# PowerDACSUB.net
KiCad netlist of a schematic drawn in Altium Designer
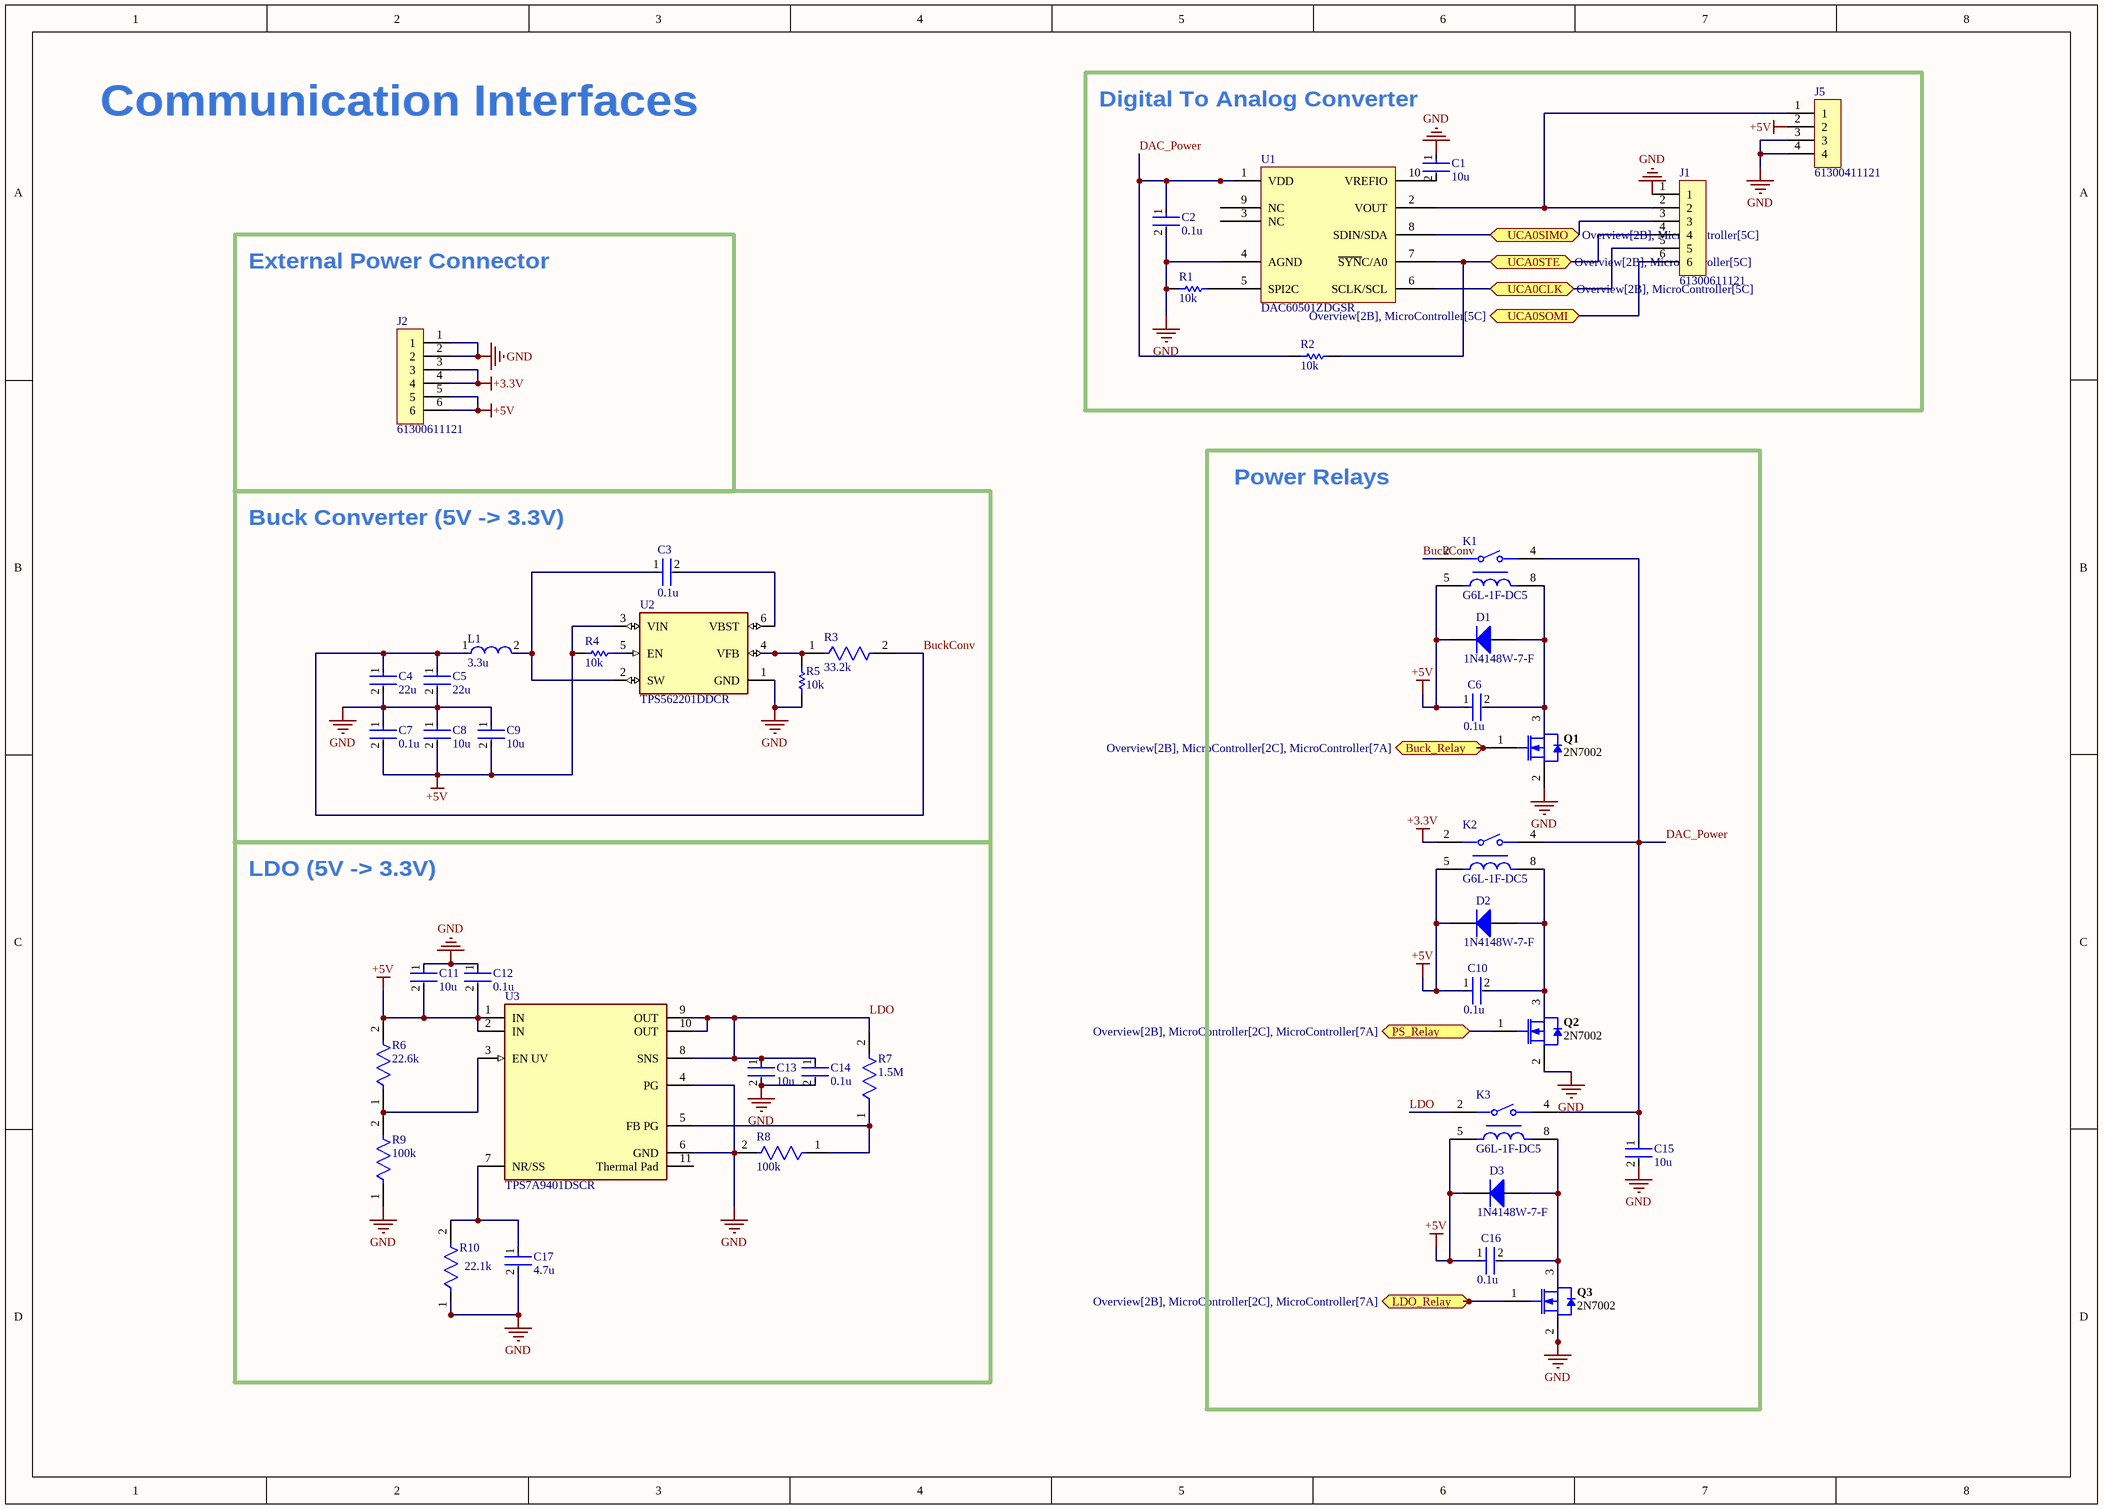
[diagram p0: PowerDACSUB.SchDoc]

(export (version "E")
  (design (tool "Eeschema 10.0.6"))
  (components
    (comp (ref "C1")
      (value "10u")
      (footprint "FP-CL21-IPC_A")
      (description "CL21 Series 0805 10uF 25V ±10% Tolerance X5R Multilayer Ceramic Chip Capacitor")
      (fields (field (name "TOLERANCE") "10%"))
      (libsource (lib "Altium Content Vault") (part "b4654b650e69147ec39a6b967a45e02"))
    )
    (comp (ref "C2")
      (value "0.1u")
      (footprint "FP-CC0805-0_85-MFG")
      (description "CAP CER 0.1UF 50V X7R 0805")
      (fields (field (name "TOLERANCE") "0.1") (field (name "MANUFACTURER PART NUMBER") "CC0805KRX7R9BB104"))
      (libsource (lib "Altium Content Vault") (part "11868f565c42a9108669ba33697ecf6"))
    )
    (comp (ref "C3")
      (value "0.1u")
      (footprint "FP-CC0805-0_85-MFG")
      (fields
        (field (name "TOLERANCE") "0.1")
        (field (name "MANUFACTURER PART NUMBER") "CC0805KRX7R9BB104")
        (field (name "MANUFACTURER") "Yageo")
      )
      (libsource (lib "Altium Content Vault") (part "11868f565c42a9108669ba33697ecf6"))
    )
    (comp (ref "C4")
      (value "22u")
      (footprint "FP-CL32-IPC_C")
      (description "Cap Ceramic 22uF 16V X7R ±10% SMD 1210 +125°C Embossed T/R")
      (fields (field (name "TOLERANCE") "10%") (field (name "VOLTAGE") "10V"))
      (libsource (lib "Altium Content Vault") (part "b4654b650e69147ec39a6b967a45e02"))
    )
    (comp (ref "C5")
      (value "22u")
      (footprint "FP-CL32-IPC_C")
      (description "Cap Ceramic 22uF 16V X7R ±10% SMD 1210 +125°C Embossed T/R")
      (fields (field (name "TOLERANCE") "10%") (field (name "VOLTAGE") "10V"))
      (libsource (lib "Altium Content Vault") (part "b4654b650e69147ec39a6b967a45e02"))
    )
    (comp (ref "C6")
      (value "0.1u")
      (footprint "FP-CC0805-0_85-MFG")
      (fields
        (field (name "TOLERANCE") "0.1")
        (field (name "MANUFACTURER PART NUMBER") "CC0805KRX7R9BB104")
        (field (name "MANUFACTURER") "Yageo")
      )
      (libsource (lib "Altium Content Vault") (part "11868f565c42a9108669ba33697ecf6"))
    )
    (comp (ref "C7")
      (value "0.1u")
      (footprint "FP-CC0805-0_85-MFG")
      (fields
        (field (name "TOLERANCE") "0.1")
        (field (name "MANUFACTURER PART NUMBER") "CC0805KRX7R9BB104")
        (field (name "MANUFACTURER") "Yageo")
      )
      (libsource (lib "Altium Content Vault") (part "11868f565c42a9108669ba33697ecf6"))
    )
    (comp (ref "C8")
      (value "10u")
      (footprint "FP-CL21-IPC_A")
      (description "CL21 Series 0805 10uF 25V ±10% Tolerance X5R Multilayer Ceramic Chip Capacitor")
      (fields (field (name "TOLERANCE") "10%"))
      (libsource (lib "Altium Content Vault") (part "b4654b650e69147ec39a6b967a45e02"))
    )
    (comp (ref "C9")
      (value "10u")
      (footprint "FP-CL21-IPC_A")
      (description "CL21 Series 0805 10uF 25V ±10% Tolerance X5R Multilayer Ceramic Chip Capacitor")
      (fields (field (name "TOLERANCE") "10%"))
      (libsource (lib "Altium Content Vault") (part "b4654b650e69147ec39a6b967a45e02"))
    )
    (comp (ref "C10")
      (value "0.1u")
      (footprint "FP-CC0805-0_85-MFG")
      (fields
        (field (name "TOLERANCE") "0.1")
        (field (name "MANUFACTURER PART NUMBER") "CC0805KRX7R9BB104")
        (field (name "MANUFACTURER") "Yageo")
      )
      (libsource (lib "Altium Content Vault") (part "11868f565c42a9108669ba33697ecf6"))
    )
    (comp (ref "C11")
      (value "10u")
      (footprint "FP-CL21-IPC_A")
      (description "CL21 Series 0805 10uF 25V ±10% Tolerance X5R Multilayer Ceramic Chip Capacitor")
      (fields (field (name "TOLERANCE") "10%"))
      (libsource (lib "Altium Content Vault") (part "b4654b650e69147ec39a6b967a45e02"))
    )
    (comp (ref "C12")
      (value "0.1u")
      (footprint "FP-CC0805-0_85-MFG")
      (description "CAP CER 0.1UF 50V X7R 0805")
      (fields (field (name "TOLERANCE") "0.1") (field (name "MANUFACTURER PART NUMBER") "CC0805KRX7R9BB104"))
      (libsource (lib "Altium Content Vault") (part "11868f565c42a9108669ba33697ecf6"))
    )
    (comp (ref "C13")
      (value "10u")
      (footprint "FP-CL21-IPC_A")
      (description "CL21 Series 0805 10uF 25V ±10% Tolerance X5R Multilayer Ceramic Chip Capacitor")
      (fields (field (name "TOLERANCE") "10%"))
      (libsource (lib "Altium Content Vault") (part "b4654b650e69147ec39a6b967a45e02"))
    )
    (comp (ref "C14")
      (value "0.1u")
      (footprint "FP-CC0805-0_85-MFG")
      (description "CAP CER 0.1UF 50V X7R 0805")
      (fields (field (name "TOLERANCE") "0.1") (field (name "MANUFACTURER PART NUMBER") "CC0805KRX7R9BB104"))
      (libsource (lib "Altium Content Vault") (part "11868f565c42a9108669ba33697ecf6"))
    )
    (comp (ref "C15")
      (value "10u")
      (footprint "FP-CL21-IPC_C")
      (description "CL21 Series 0805 10uF 10V ±20% Tolerance X5R Multilayer Ceramic Chip Capacitor")
      (fields (field (name "TOLERANCE") "20%"))
      (libsource (lib "Altium Content Vault") (part "b4654b650e69147ec39a6b967a45e02"))
    )
    (comp (ref "C16")
      (value "0.1u")
      (footprint "FP-CC0805-0_85-MFG")
      (fields
        (field (name "TOLERANCE") "0.1")
        (field (name "MANUFACTURER PART NUMBER") "CC0805KRX7R9BB104")
        (field (name "MANUFACTURER") "Yageo")
      )
      (libsource (lib "Altium Content Vault") (part "11868f565c42a9108669ba33697ecf6"))
    )
    (comp (ref "C17")
      (value "4.7u")
      (footprint "FP-CL21-IPC_A")
      (description "CL21 Series 0805 4.7uF 25V ±10% Tolerance X5R Multilayer Ceramic Chip Capacitor")
      (fields (field (name "TOLERANCE") "10%"))
      (libsource (lib "Altium Content Vault") (part "b4654b650e69147ec39a6b967a45e02"))
    )
    (comp (ref "D1")
      (value "1N4148W-7-F")
      (footprint "DIOD-SOD123-2_V")
      (description "Fast Switching Diode, 100 V, 0.15 A, -65 to 150 degC, 2-Pin?SOD123, RoHS, Tape and Reel")
      (fields (field (name "MANUFACTURER") "DiodesIncorporated"))
      (libsource (lib "Altium Content Vault") (part "D-AK-2"))
    )
    (comp (ref "D2")
      (value "1N4148W-7-F")
      (footprint "DIOD-SOD123-2_V")
      (description "Fast Switching Diode, 100 V, 0.15 A, -65 to 150 degC, 2-Pin?SOD123, RoHS, Tape and Reel")
      (fields (field (name "MANUFACTURER") "DiodesIncorporated"))
      (libsource (lib "Altium Content Vault") (part "D-AK-2"))
    )
    (comp (ref "D3")
      (value "1N4148W-7-F")
      (footprint "DIOD-SOD123-2_V")
      (description "Fast Switching Diode, 100 V, 0.15 A, -65 to 150 degC, 2-Pin?SOD123, RoHS, Tape and Reel")
      (fields (field (name "MANUFACTURER") "DiodesIncorporated"))
      (libsource (lib "Altium Content Vault") (part "D-AK-2"))
    )
    (comp (ref "J1")
      (value "61300611121")
      (footprint "61300611121")
      (description "CONN HEADER VERT 6POS 2.54MM")
      (libsource (lib "") (part "61300611121_1"))
    )
    (comp (ref "J2")
      (value "61300611121")
      (footprint "61300611121")
      (description "CONN HEADER VERT 6POS 2.54MM")
      (libsource (lib "Schlib1") (part "61300611121"))
    )
    (comp (ref "J5")
      (value "61300411121")
      (footprint "61300411121")
      (description "Connector Header Through Hole 4 position 0.100\" (2.54mm)")
      (libsource (lib "Schlib1") (part "61300411121"))
    )
    (comp (ref "K1")
      (value "G6L-1F-DC5")
      (footprint "FP-G6L-1F-DC5-MFG")
      (description "RELAY TELECOM SPST 1A 5VDC")
      (fields
        (field (name "MANUFACTURER") "Omron")
        (field (name "OCTOPART") "https://octopart.com/g6l-1f+dc5-omron-18903080")
      )
      (libsource (lib "Altium Content Vault") (part "0b4cad2df39780911da7817dc4dbd4a"))
    )
    (comp (ref "K2")
      (value "G6L-1F-DC5")
      (footprint "FP-G6L-1F-DC5-MFG")
      (description "RELAY TELECOM SPST 1A 5VDC")
      (fields
        (field (name "MANUFACTURER") "Omron")
        (field (name "OCTOPART") "https://octopart.com/g6l-1f+dc5-omron-18903080")
      )
      (libsource (lib "Altium Content Vault") (part "0b4cad2df39780911da7817dc4dbd4a"))
    )
    (comp (ref "K3")
      (value "G6L-1F-DC5")
      (footprint "FP-G6L-1F-DC5-MFG")
      (description "RELAY TELECOM SPST 1A 5VDC")
      (fields
        (field (name "MANUFACTURER") "Omron")
        (field (name "OCTOPART") "https://octopart.com/g6l-1f+dc5-omron-18903080")
      )
      (libsource (lib "Altium Content Vault") (part "0b4cad2df39780911da7817dc4dbd4a"))
    )
    (comp (ref "L1")
      (value "3.3u")
      (footprint "FP-NR4018-MFG")
      (description "SMD Power Inductors 3.3uH ±20% 2A 66mΩ")
      (fields (field (name "TOLERANCE") "20%"))
      (libsource (lib "Altium Content Vault") (part "725321dda6339637d4d059423bc1c3c"))
    )
    (comp (ref "Q1")
      (value "2N7002")
      (footprint "INF-PG-SOT23_M")
      (fields (field (name "MANUFACTURER") "Infineon"))
      (libsource (lib "Altium Content Vault") (part "INF-NDMOS-GSD-3"))
    )
    (comp (ref "Q2")
      (value "2N7002")
      (footprint "INF-PG-SOT23_M")
      (fields (field (name "MANUFACTURER") "Infineon"))
      (libsource (lib "Altium Content Vault") (part "INF-NDMOS-GSD-3"))
    )
    (comp (ref "Q3")
      (value "2N7002")
      (footprint "INF-PG-SOT23_M")
      (fields (field (name "MANUFACTURER") "Infineon"))
      (libsource (lib "Altium Content Vault") (part "INF-NDMOS-GSD-3"))
    )
    (comp (ref "R1")
      (value "10k")
      (footprint "RESC1609X50X30ML10T20")
      (fields (field (name "MANUFACTURER") "Vishay Dale") (field (name "PART NUMBER") "CRCW060310K0FKTB"))
      (libsource (lib "Altium Content Vault") (part "RES"))
    )
    (comp (ref "R2")
      (value "10k")
      (footprint "RESC1609X50X30ML10T20")
      (fields (field (name "MANUFACTURER") "Vishay Dale") (field (name "PART NUMBER") "CRCW060310K0FKTB"))
      (libsource (lib "Altium Content Vault") (part "RES"))
    )
    (comp (ref "R3")
      (value "33.2k")
      (footprint "FP-CR0805-IPC_C")
      (description "Thick Film Chip Resistors 0805 33.2kΩ 0.125W 1% 100ppm/°C")
      (fields (field (name "TOLERANCE") "1%"))
      (libsource (lib "Altium Content Vault") (part "1029c3af85768c4190bb7ad29bc67b5"))
    )
    (comp (ref "R4")
      (value "10k")
      (footprint "RESC1609X50X30ML10T20")
      (fields (field (name "MANUFACTURER") "Vishay Dale") (field (name "PART NUMBER") "CRCW060310K0FKTB"))
      (libsource (lib "Altium Content Vault") (part "RES"))
    )
    (comp (ref "R5")
      (value "10k")
      (footprint "RESC1609X50X30ML10T20")
      (fields (field (name "MANUFACTURER") "Vishay Dale") (field (name "PART NUMBER") "CRCW060310K0FKTB"))
      (libsource (lib "Altium Content Vault") (part "RES"))
    )
    (comp (ref "R6")
      (value "22.6k")
      (footprint "FP-RT0805-MFG")
      (description "RES SMD 22.6K OHM 1% 1/8W 0805")
      (fields
        (field (name "OCTOPART") "https://octopart.com/rt0805fre0722k6l-yageo-1479006")
        (field (name "TOLERANCE") "0.0001")
      )
      (libsource (lib "Altium Content Vault") (part "1029c3af85768c4190bb7ad29bc67b5"))
    )
    (comp (ref "R7")
      (value "1.5M")
      (footprint "FP-MCR03-IPC_B")
      (description "Thick Film Chip Resistor, 0603, 1.5MΩ, 1%, 100ppm/°C, 0.1W, 50V")
      (fields (field (name "TOLERANCE") "1%"))
      (libsource (lib "Altium Content Vault") (part "1029c3af85768c4190bb7ad29bc67b5"))
    )
    (comp (ref "R8")
      (value "100k")
      (footprint "FP-RK73H1J-IPC_C")
      (description "100kΩ ±1% 0.1W Chip Resistor 0603 Thick Film AEC-Q200 Qualified")
      (fields (field (name "TOLERANCE") "1%"))
      (libsource (lib "Altium Content Vault") (part "1029c3af85768c4190bb7ad29bc67b5"))
    )
    (comp (ref "R9")
      (value "100k")
      (footprint "FP-RK73H1J-IPC_C")
      (description "100kΩ ±1% 0.1W Chip Resistor 0603 Thick Film AEC-Q200 Qualified")
      (fields (field (name "TOLERANCE") "1%"))
      (libsource (lib "Altium Content Vault") (part "1029c3af85768c4190bb7ad29bc67b5"))
    )
    (comp (ref "R10")
      (value "22.1k")
      (footprint "FP-CRCW0805-e3-IPC_C")
      (description "RES Thick Film, 22.1kΩ, 1%, 0.125W, 100ppm/°C, 0805")
      (fields (field (name "TOLERANCE") "1%"))
      (libsource (lib "Altium Content Vault") (part "1029c3af85768c4190bb7ad29bc67b5"))
    )
    (comp (ref "U1")
      (value "DAC60501ZDGSR")
      (footprint "DAC60501ZDGSR")
      (libsource (lib "DAC60501ZDGSR") (part "DAC60501ZDGSR"))
    )
    (comp (ref "U2")
      (value "TPS562201DDCR")
      (footprint "FP-DDC0006A-IPC_C")
      (description "IC REG BUCK ADJ 2A TSOT23-6")
      (libsource (lib "Altium Content Vault") (part "957e164956730ea4bf6293280af19fc"))
    )
    (comp (ref "U3")
      (value "TPS7A9401DSCR")
      (footprint "FP-DSC0010J-MFG")
      (description "1-A, ULTRA-LOW NOISE, ULTRA-HIGH")
      (libsource (lib "Altium Content Vault") (part "a6308bcaf518fe2c6c22e77077fd2b2"))
    )
  )
  (nets
    (net (code "1") (name "+3.3V") (class "Default")
      (node (ref "J2") (pin "3") (pinfunction "3_3") (pintype "passive"))
      (node (ref "J2") (pin "4") (pinfunction "4_4") (pintype "passive"))
      (node (ref "K2") (pin "2") (pinfunction "2_2") (pintype "passive"))
    )
    (net (code "2") (name "+5V") (class "Default")
      (node (ref "C10") (pin "1") (pinfunction "1_1") (pintype "passive"))
      (node (ref "C11") (pin "2") (pinfunction "2_2") (pintype "passive"))
      (node (ref "C12") (pin "2") (pinfunction "2_2") (pintype "passive"))
      (node (ref "C16") (pin "1") (pinfunction "1_1") (pintype "passive"))
      (node (ref "C6") (pin "1") (pinfunction "1_1") (pintype "passive"))
      (node (ref "C7") (pin "2") (pinfunction "2_2") (pintype "passive"))
      (node (ref "C8") (pin "2") (pinfunction "2_2") (pintype "passive"))
      (node (ref "C9") (pin "2") (pinfunction "2_2") (pintype "passive"))
      (node (ref "D1") (pin "2") (pinfunction "K_2") (pintype "passive"))
      (node (ref "D2") (pin "2") (pinfunction "K_2") (pintype "passive"))
      (node (ref "D3") (pin "2") (pinfunction "K_2") (pintype "passive"))
      (node (ref "J2") (pin "5") (pinfunction "5_5") (pintype "passive"))
      (node (ref "J2") (pin "6") (pinfunction "6_6") (pintype "passive"))
      (node (ref "J5") (pin "2") (pinfunction "2_2") (pintype "passive"))
      (node (ref "K1") (pin "5") (pinfunction "5_5") (pintype "passive"))
      (node (ref "K2") (pin "5") (pinfunction "5_5") (pintype "passive"))
      (node (ref "K3") (pin "5") (pinfunction "5_5") (pintype "passive"))
      (node (ref "R4") (pin "2") (pinfunction "2_2") (pintype "passive"))
      (node (ref "R6") (pin "2") (pinfunction "2_2") (pintype "passive"))
      (node (ref "U2") (pin "3") (pinfunction "VIN_3") (pintype "bidirectional"))
      (node (ref "U3") (pin "1") (pinfunction "IN_1") (pintype "power_in"))
      (node (ref "U3") (pin "2") (pinfunction "IN_2") (pintype "power_in"))
    )
    (net (code "3") (name "/BuckConv") (class "Default")
      (node (ref "C4") (pin "1") (pinfunction "1_1") (pintype "passive"))
      (node (ref "C5") (pin "1") (pinfunction "1_1") (pintype "passive"))
      (node (ref "K1") (pin "2") (pinfunction "2_2") (pintype "passive"))
      (node (ref "L1") (pin "1") (pinfunction "1_1") (pintype "passive"))
      (node (ref "R3") (pin "2") (pinfunction "2_2") (pintype "passive"))
    )
    (net (code "4") (name "/Buck_Relay") (class "Default")
      (node (ref "Q1") (pin "1") (pinfunction "GATE_1") (pintype "passive"))
    )
    (net (code "5") (name "/DAC_Power") (class "Default")
      (node (ref "C15") (pin "1") (pinfunction "1_1") (pintype "passive"))
      (node (ref "C2") (pin "1") (pinfunction "1_1") (pintype "passive"))
      (node (ref "K1") (pin "4") (pinfunction "4_4") (pintype "passive"))
      (node (ref "K2") (pin "4") (pinfunction "4_4") (pintype "passive"))
      (node (ref "K3") (pin "4") (pinfunction "4_4") (pintype "passive"))
      (node (ref "R2") (pin "1") (pinfunction "1_1") (pintype "passive"))
      (node (ref "U1") (pin "1") (pinfunction "VDD_1") (pintype "passive"))
    )
    (net (code "6") (name "/LDO") (class "Default")
      (node (ref "C13") (pin "1") (pinfunction "1_1") (pintype "passive"))
      (node (ref "C14") (pin "1") (pinfunction "1_1") (pintype "passive"))
      (node (ref "K3") (pin "2") (pinfunction "2_2") (pintype "passive"))
      (node (ref "R7") (pin "2") (pinfunction "2_2") (pintype "passive"))
      (node (ref "U3") (pin "10") (pinfunction "OUT_10") (pintype "power_in"))
      (node (ref "U3") (pin "8") (pinfunction "SNS_8") (pintype "passive"))
      (node (ref "U3") (pin "9") (pinfunction "OUT_9") (pintype "power_in"))
    )
    (net (code "7") (name "/LDO_Relay") (class "Default")
      (node (ref "Q3") (pin "1") (pinfunction "GATE_1") (pintype "passive"))
    )
    (net (code "8") (name "/PS_Relay") (class "Default")
      (node (ref "Q2") (pin "1") (pinfunction "GATE_1") (pintype "passive"))
    )
    (net (code "9") (name "/UCA0CLK") (class "Default")
      (node (ref "J1") (pin "5") (pinfunction "5_5") (pintype "passive"))
      (node (ref "U1") (pin "6") (pinfunction "SCLK/SCL_6") (pintype "passive"))
    )
    (net (code "10") (name "/UCA0SIMO") (class "Default")
      (node (ref "J1") (pin "3") (pinfunction "3_3") (pintype "passive"))
      (node (ref "U1") (pin "8") (pinfunction "SDIN/SDA_8") (pintype "passive"))
    )
    (net (code "11") (name "/UCA0SOMI") (class "Default")
      (node (ref "J1") (pin "6") (pinfunction "6_6") (pintype "passive"))
    )
    (net (code "12") (name "/UCA0STE") (class "Default")
      (node (ref "J1") (pin "4") (pinfunction "4_4") (pintype "passive"))
      (node (ref "R2") (pin "2") (pinfunction "2_2") (pintype "passive"))
      (node (ref "U1") (pin "7") (pinfunction "~{SYN}C/A0_7") (pintype "passive"))
    )
    (net (code "13") (name "GND") (class "Default")
      (node (ref "C1") (pin "1") (pinfunction "1_1") (pintype "passive"))
      (node (ref "C11") (pin "1") (pinfunction "1_1") (pintype "passive"))
      (node (ref "C12") (pin "1") (pinfunction "1_1") (pintype "passive"))
      (node (ref "C13") (pin "2") (pinfunction "2_2") (pintype "passive"))
      (node (ref "C14") (pin "2") (pinfunction "2_2") (pintype "passive"))
      (node (ref "C15") (pin "2") (pinfunction "2_2") (pintype "passive"))
      (node (ref "C17") (pin "2") (pinfunction "2_2") (pintype "passive"))
      (node (ref "C2") (pin "2") (pinfunction "2_2") (pintype "passive"))
      (node (ref "C4") (pin "2") (pinfunction "2_2") (pintype "passive"))
      (node (ref "C5") (pin "2") (pinfunction "2_2") (pintype "passive"))
      (node (ref "C7") (pin "1") (pinfunction "1_1") (pintype "passive"))
      (node (ref "C8") (pin "1") (pinfunction "1_1") (pintype "passive"))
      (node (ref "C9") (pin "1") (pinfunction "1_1") (pintype "passive"))
      (node (ref "J1") (pin "1") (pinfunction "1_1") (pintype "passive"))
      (node (ref "J2") (pin "1") (pinfunction "1_1") (pintype "passive"))
      (node (ref "J2") (pin "2") (pinfunction "2_2") (pintype "passive"))
      (node (ref "J5") (pin "3") (pinfunction "3_3") (pintype "passive"))
      (node (ref "J5") (pin "4") (pinfunction "4_4") (pintype "passive"))
      (node (ref "Q1") (pin "2") (pinfunction "SOURCE_2") (pintype "passive"))
      (node (ref "Q2") (pin "2") (pinfunction "SOURCE_2") (pintype "passive"))
      (node (ref "Q3") (pin "2") (pinfunction "SOURCE_2") (pintype "passive"))
      (node (ref "R1") (pin "1") (pinfunction "1_1") (pintype "passive"))
      (node (ref "R10") (pin "1") (pinfunction "1_1") (pintype "passive"))
      (node (ref "R5") (pin "1") (pinfunction "1_1") (pintype "passive"))
      (node (ref "R8") (pin "2") (pinfunction "2_2") (pintype "passive"))
      (node (ref "R9") (pin "1") (pinfunction "1_1") (pintype "passive"))
      (node (ref "U1") (pin "4") (pinfunction "AGND_4") (pintype "passive"))
      (node (ref "U2") (pin "1") (pinfunction "GND_1") (pintype "power_in"))
      (node (ref "U3") (pin "4") (pinfunction "PG_4") (pintype "passive"))
      (node (ref "U3") (pin "6") (pinfunction "GND_6") (pintype "power_in"))
    )
    (net (code "14") (name "Net-(D1-A)") (class "Default")
      (node (ref "C6") (pin "2") (pinfunction "2_2") (pintype "passive"))
      (node (ref "D1") (pin "1") (pinfunction "A_1") (pintype "passive"))
      (node (ref "K1") (pin "8") (pinfunction "8_8") (pintype "passive"))
      (node (ref "Q1") (pin "3") (pinfunction "DRAIN_3") (pintype "passive"))
    )
    (net (code "15") (name "Net-(D2-A)") (class "Default")
      (node (ref "C10") (pin "2") (pinfunction "2_2") (pintype "passive"))
      (node (ref "D2") (pin "1") (pinfunction "A_1") (pintype "passive"))
      (node (ref "K2") (pin "8") (pinfunction "8_8") (pintype "passive"))
      (node (ref "Q2") (pin "3") (pinfunction "DRAIN_3") (pintype "passive"))
    )
    (net (code "16") (name "Net-(D3-A)") (class "Default")
      (node (ref "C16") (pin "2") (pinfunction "2_2") (pintype "passive"))
      (node (ref "D3") (pin "1") (pinfunction "A_1") (pintype "passive"))
      (node (ref "K3") (pin "8") (pinfunction "8_8") (pintype "passive"))
      (node (ref "Q3") (pin "3") (pinfunction "DRAIN_3") (pintype "passive"))
    )
    (net (code "17") (name "Net-(U1-SPI2C)") (class "Default")
      (node (ref "R1") (pin "2") (pinfunction "2_2") (pintype "passive"))
      (node (ref "U1") (pin "5") (pinfunction "SPI2C_5") (pintype "passive"))
    )
    (net (code "18") (name "Net-(U1-VOUT)") (class "Default")
      (node (ref "J1") (pin "2") (pinfunction "2_2") (pintype "passive"))
      (node (ref "J5") (pin "1") (pinfunction "1_1") (pintype "passive"))
      (node (ref "U1") (pin "2") (pinfunction "VOUT_2") (pintype "passive"))
    )
    (net (code "19") (name "Net-(U1-VREFIO)") (class "Default")
      (node (ref "C1") (pin "2") (pinfunction "2_2") (pintype "passive"))
      (node (ref "U1") (pin "10") (pinfunction "VREFIO_10") (pintype "passive"))
    )
    (net (code "20") (name "Net-(U2-EN)") (class "Default")
      (node (ref "R4") (pin "1") (pinfunction "1_1") (pintype "passive"))
      (node (ref "U2") (pin "5") (pinfunction "EN_5") (pintype "input"))
    )
    (net (code "21") (name "Net-(U2-SW)") (class "Default")
      (node (ref "C3") (pin "1") (pinfunction "1_1") (pintype "passive"))
      (node (ref "L1") (pin "2") (pinfunction "2_2") (pintype "passive"))
      (node (ref "U2") (pin "2") (pinfunction "SW_2") (pintype "bidirectional"))
    )
    (net (code "22") (name "Net-(U2-VBST)") (class "Default")
      (node (ref "C3") (pin "2") (pinfunction "2_2") (pintype "passive"))
      (node (ref "U2") (pin "6") (pinfunction "VBST_6") (pintype "bidirectional"))
    )
    (net (code "23") (name "Net-(U2-VFB)") (class "Default")
      (node (ref "R3") (pin "1") (pinfunction "1_1") (pintype "passive"))
      (node (ref "R5") (pin "2") (pinfunction "2_2") (pintype "passive"))
      (node (ref "U2") (pin "4") (pinfunction "VFB_4") (pintype "bidirectional"))
    )
    (net (code "24") (name "Net-(U3-EN_UV)") (class "Default")
      (node (ref "R6") (pin "1") (pinfunction "1_1") (pintype "passive"))
      (node (ref "R9") (pin "2") (pinfunction "2_2") (pintype "passive"))
      (node (ref "U3") (pin "3") (pinfunction "EN_UV_3") (pintype "input"))
    )
    (net (code "25") (name "Net-(U3-FB_PG)") (class "Default")
      (node (ref "R7") (pin "1") (pinfunction "1_1") (pintype "passive"))
      (node (ref "R8") (pin "1") (pinfunction "1_1") (pintype "passive"))
      (node (ref "U3") (pin "5") (pinfunction "FB_PG_5") (pintype "passive"))
    )
    (net (code "26") (name "Net-(U3-NR{slash}SS)") (class "Default")
      (node (ref "C17") (pin "1") (pinfunction "1_1") (pintype "passive"))
      (node (ref "R10") (pin "2") (pinfunction "2_2") (pintype "passive"))
      (node (ref "U3") (pin "7") (pinfunction "NR/SS_7") (pintype "passive"))
    )
    (net (code "27") (name "unconnected-(U1-NC-Pad3)") (class "Default")
      (node (ref "U1") (pin "3") (pinfunction "NC_3") (pintype "passive"))
    )
    (net (code "28") (name "unconnected-(U1-NC-Pad9)") (class "Default")
      (node (ref "U1") (pin "9") (pinfunction "NC_9") (pintype "passive"))
    )
    (net (code "29") (name "unconnected-(U3-Thermal_Pad-Pad11)") (class "Default")
      (node (ref "U3") (pin "11") (pinfunction "Thermal_Pad_11") (pintype "power_in"))
    )
  )
)
